# real-time-clock.net
KiCad netlist of a schematic drawn in Altium Designer
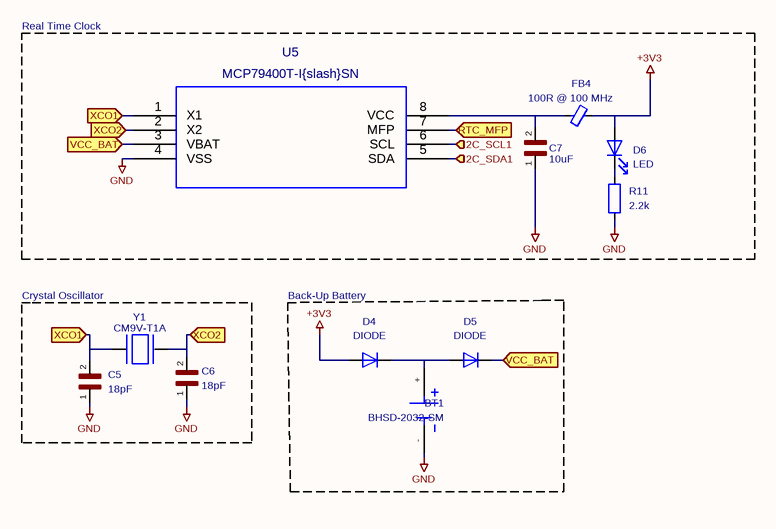
[diagram p0: real-time-clock.SchDoc]

(export (version "E")
  (design (tool "Eeschema 10.0.6"))
  (components
    (comp (ref "BT1")
      (value "BHSD-2032-SM")
      (fields (field (name "MANUFACTURER") "Memory Protection Devices, Inc."))
      (libsource (lib "Daughterboard_Symbols") (part "BVSD-2032-PC"))
    )
    (comp (ref "C5") (value "18pF") (libsource (lib "Daughterboard_Symbols") (part "CL10B104KB8NNNL")))
    (comp (ref "C6") (value "18pF") (libsource (lib "Daughterboard_Symbols") (part "CL10B104KB8NNNL")))
    (comp (ref "C7") (value "10uF") (libsource (lib "Daughterboard_Symbols") (part "CL10B104KB8NNNL")))
    (comp (ref "D4") (value "DIODE") (libsource (lib "Simulation_SPICE") (part "DIODE")))
    (comp (ref "D5") (value "DIODE") (libsource (lib "Simulation_SPICE") (part "DIODE")))
    (comp (ref "D6") (value "LED") (libsource (lib "Device") (part "LED")))
    (comp (ref "FB4") (value "100R @ 100 MHz") (libsource (lib "Device") (part "FerriteBead_Small")))
    (comp (ref "R11") (value "2.2k") (libsource (lib "Device") (part "R")))
    (comp (ref "U5")
      (value "MCP79400T-I/SN")
      (libsource (lib "Daughterboard_Symbols") (part "MCP79400T-I{brace}slash}SN"))
    )
    (comp (ref "Y1")
      (value "CM9V-T1A")
      (fields (field (name "MANUFACTURER") "Micro Crystal"))
      (libsource (lib "CM9V-T1A-32") (part "CM9V-T1A-32.768KHZ-9PF-20PPM-TA-QC"))
    )
  )
  (nets
    (net (code "1") (name "+3V3") (class "Default")
      (node (ref "D4") (pin "1") (pinfunction "A_1") (pintype "passive"))
      (node (ref "D6") (pin "2") (pinfunction "A_2") (pintype "passive"))
      (node (ref "FB4") (pin "1") (pinfunction "1_1") (pintype "passive"))
    )
    (net (code "2") (name "/I2C_SCL1") (class "Default")
      (node (ref "U5") (pin "6") (pinfunction "SCL_6") (pintype "passive"))
    )
    (net (code "3") (name "/I2C_SDA1") (class "Default")
      (node (ref "U5") (pin "5") (pinfunction "SDA_5") (pintype "passive"))
    )
    (net (code "4") (name "/RTC_MFP") (class "Default")
      (node (ref "U5") (pin "7") (pinfunction "MFP_7") (pintype "passive"))
    )
    (net (code "5") (name "/VCC_BAT") (class "Default")
      (node (ref "D5") (pin "2") (pinfunction "K_2") (pintype "passive"))
      (node (ref "U5") (pin "3") (pinfunction "VBAT_3") (pintype "passive"))
    )
    (net (code "6") (name "/XCO1") (class "Default")
      (node (ref "C5") (pin "2") (pinfunction "2_2") (pintype "passive"))
      (node (ref "U5") (pin "1") (pinfunction "X1_1") (pintype "passive"))
      (node (ref "Y1") (pin "1") (pinfunction "1_1") (pintype "passive"))
    )
    (net (code "7") (name "/XCO2") (class "Default")
      (node (ref "C6") (pin "2") (pinfunction "2_2") (pintype "passive"))
      (node (ref "U5") (pin "2") (pinfunction "X2_2") (pintype "passive"))
      (node (ref "Y1") (pin "2") (pinfunction "2_2") (pintype "passive"))
    )
    (net (code "8") (name "GND") (class "Default")
      (node (ref "BT1") (pin "-") (pinfunction "-_-") (pintype "passive"))
      (node (ref "C5") (pin "1") (pinfunction "1_1") (pintype "passive"))
      (node (ref "C6") (pin "1") (pinfunction "1_1") (pintype "passive"))
      (node (ref "C7") (pin "1") (pinfunction "1_1") (pintype "passive"))
      (node (ref "R11") (pin "2") (pinfunction "2_2") (pintype "passive"))
      (node (ref "U5") (pin "4") (pinfunction "VSS_4") (pintype "passive"))
    )
    (net (code "9") (name "Net-(D4-K)") (class "Default")
      (node (ref "BT1") (pin "+") (pinfunction "+_+") (pintype "passive"))
      (node (ref "D4") (pin "2") (pinfunction "K_2") (pintype "passive"))
      (node (ref "D5") (pin "1") (pinfunction "A_1") (pintype "passive"))
    )
    (net (code "10") (name "Net-(D6-K)") (class "Default")
      (node (ref "D6") (pin "1") (pinfunction "K_1") (pintype "passive"))
      (node (ref "R11") (pin "1") (pinfunction "1_1") (pintype "passive"))
    )
    (net (code "11") (name "Net-(U5-VCC)") (class "Default")
      (node (ref "C7") (pin "2") (pinfunction "2_2") (pintype "passive"))
      (node (ref "FB4") (pin "2") (pinfunction "2_2") (pintype "passive"))
      (node (ref "U5") (pin "8") (pinfunction "VCC_8") (pintype "passive"))
    )
  )
)
